# SCH_TabletComputer-SurfacePi_2024-07-24.net
KiCad netlist of a schematic drawn in EasyEDA
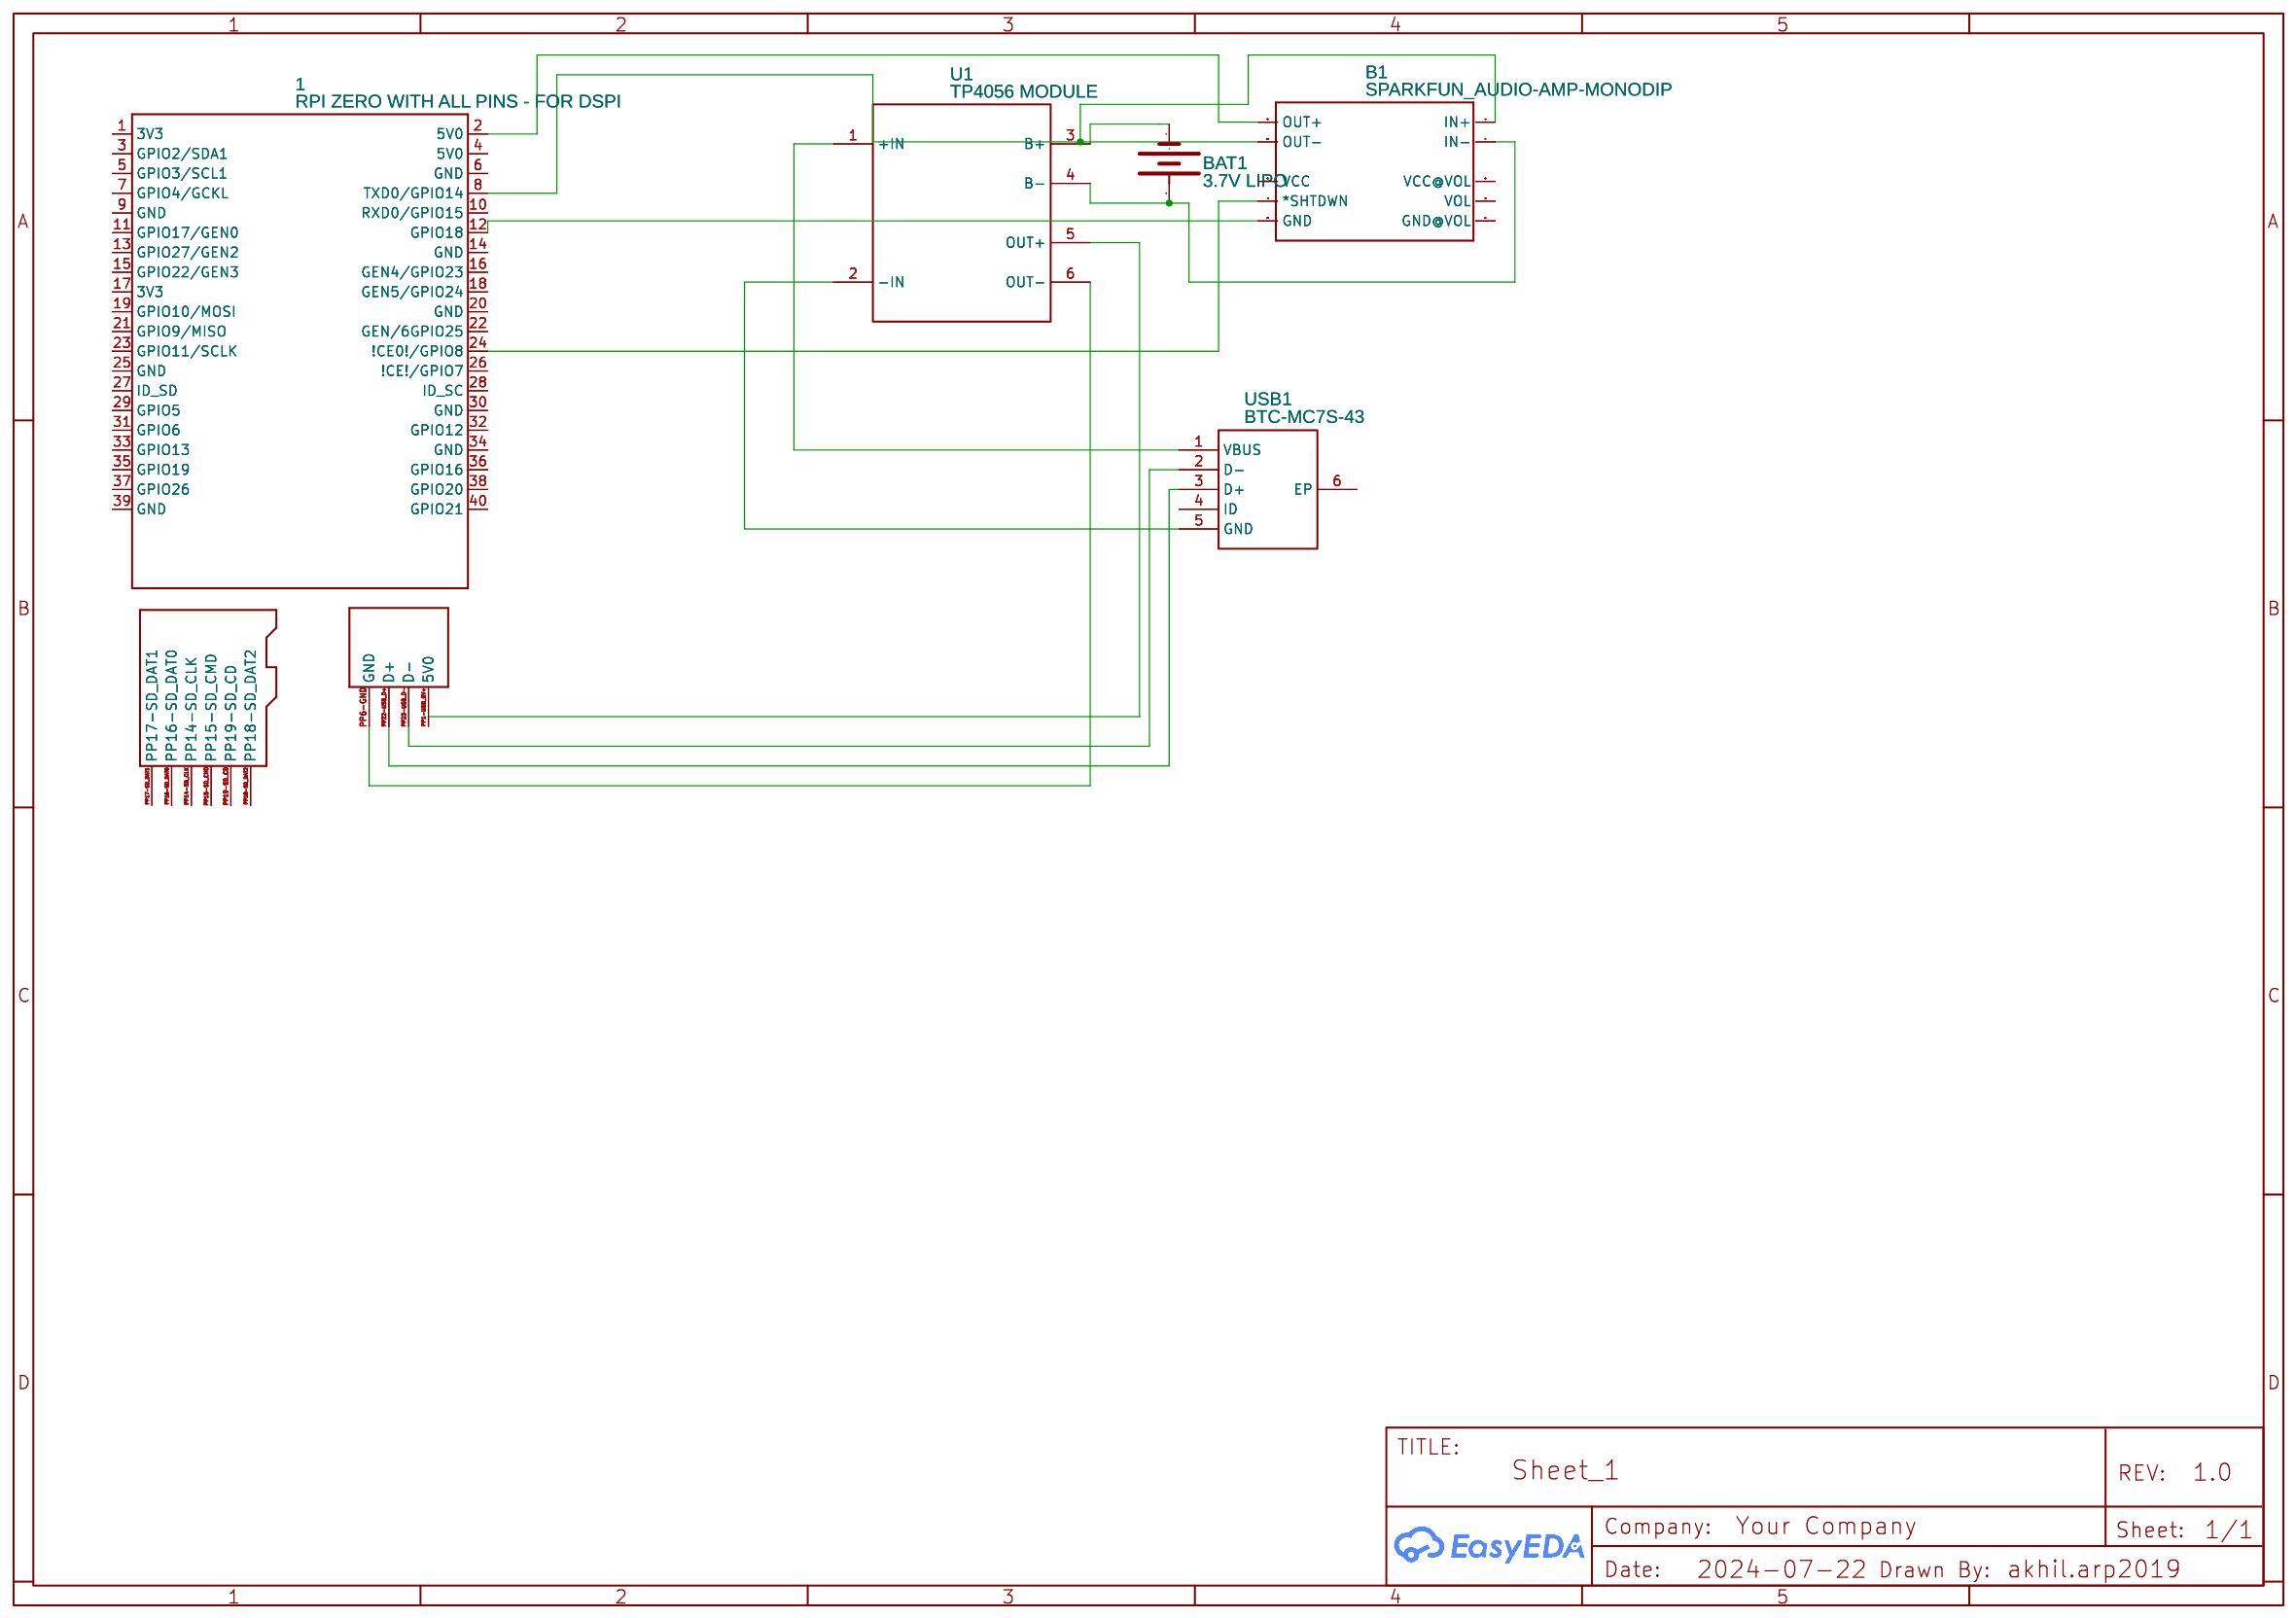
[diagram p0: schematic sheet]

(export (version "E")
  (design (tool "Eeschema 10.0.6"))
  (components
    (comp (ref "1")
      (value "RPI ZERO WITH ALL PINS - FOR DSPI")
      (libsource (lib "") (part "RPI ZERO WITH ALL PINS - FOR DSPI"))
    )
    (comp (ref "B1")
      (value "SPARKFUN_AUDIO-AMP-MONODIP")
      (libsource (lib "") (part "SPARKFUN_AUDIO-AMP-MONODIP"))
    )
    (comp (ref "BAT1") (value "3.7V LIPO") (libsource (lib "") (part "3.7V LIPO")))
    (comp (ref "U1") (value "TP4056 MODULE") (libsource (lib "") (part "TP4056 MODULE")))
    (comp (ref "USB1")
      (value "BTC-MC7S-43")
      (fields (field (name "Manufacturer") "DGBZ(东莞博众)"))
      (libsource (lib "") (part "BTC-MC7S-43"))
    )
  )
  (nets
    (net (code "1") (name "Net-(1-!CE0!{slash}GPIO8)") (class "Default")
      (node (ref "1") (pin "24") (pinfunction "!CE0!/GPIO8_24") (pintype "bidirectional"))
      (node (ref "B1") (pin "S") (pinfunction "*SHTDWN_S") (pintype "bidirectional"))
    )
    (net (code "2") (name "Net-(1-5V0-Pad2)") (class "Default")
      (node (ref "1") (pin "2") (pinfunction "5V0_2") (pintype "bidirectional"))
      (node (ref "B1") (pin "OUT+") (pinfunction "OUT+_OUT+") (pintype "bidirectional"))
    )
    (net (code "3") (name "Net-(1-D+)") (class "Default")
      (node (ref "1") (pin "PP22-USB_D+") (pinfunction "D+_PP22-USB_D+") (pintype "bidirectional"))
      (node (ref "USB1") (pin "3") (pinfunction "D+_3") (pintype "unspecified"))
    )
    (net (code "4") (name "Net-(1-D-)") (class "Default")
      (node (ref "1") (pin "PP23-USB_D-") (pinfunction "D-_PP23-USB_D-") (pintype "bidirectional"))
      (node (ref "USB1") (pin "2") (pinfunction "D-_2") (pintype "unspecified"))
    )
    (net (code "5") (name "Net-(1-GPIO18)") (class "Default")
      (node (ref "1") (pin "12") (pinfunction "GPIO18_12") (pintype "bidirectional"))
      (node (ref "B1") (pin "PWR-") (pinfunction "GND_PWR-") (pintype "bidirectional"))
    )
    (net (code "6") (name "Net-(1-TXD0{slash}GPIO14)") (class "Default")
      (node (ref "1") (pin "8") (pinfunction "TXD0/GPIO14_8") (pintype "bidirectional"))
      (node (ref "B1") (pin "IN+") (pinfunction "IN+_IN+") (pintype "bidirectional"))
      (node (ref "B1") (pin "OUT-") (pinfunction "OUT-_OUT-") (pintype "bidirectional"))
    )
    (net (code "7") (name "Net-(U1-+IN)") (class "Default")
      (node (ref "U1") (pin "1") (pinfunction "+IN_1") (pintype "unspecified"))
      (node (ref "USB1") (pin "1") (pinfunction "VBUS_1") (pintype "unspecified"))
    )
    (net (code "8") (name "Net-(U1--IN)") (class "Default")
      (node (ref "U1") (pin "2") (pinfunction "-IN_2") (pintype "unspecified"))
      (node (ref "USB1") (pin "5") (pinfunction "GND_5") (pintype "unspecified"))
    )
    (net (code "9") (name "Net-(U1-B+)") (class "Default")
      (node (ref "BAT1") (pin "-") (pinfunction "-_-") (pintype "passive"))
      (node (ref "U1") (pin "3") (pinfunction "B+_3") (pintype "unspecified"))
    )
    (net (code "10") (name "Net-(U1-B-)") (class "Default")
      (node (ref "B1") (pin "IN-") (pinfunction "IN-_IN-") (pintype "bidirectional"))
      (node (ref "BAT1") (pin "+") (pinfunction "+_+") (pintype "passive"))
      (node (ref "U1") (pin "4") (pinfunction "B-_4") (pintype "unspecified"))
    )
    (net (code "11") (name "Net-(U1-OUT+)") (class "Default")
      (node (ref "1") (pin "PP1-USB_5V+") (pinfunction "5V0_PP1-USB_5V+") (pintype "bidirectional"))
      (node (ref "U1") (pin "5") (pinfunction "OUT+_5") (pintype "unspecified"))
    )
    (net (code "12") (name "Net-(U1-OUT-)") (class "Default")
      (node (ref "1") (pin "PP6-GND") (pinfunction "GND_PP6-GND") (pintype "bidirectional"))
      (node (ref "U1") (pin "6") (pinfunction "OUT-_6") (pintype "unspecified"))
    )
    (net (code "13") (name "unconnected-(1-!CE!{slash}GPIO7-Pad26)") (class "Default")
      (node (ref "1") (pin "26") (pinfunction "!CE!/GPIO7_26") (pintype "bidirectional"))
    )
    (net (code "14") (name "unconnected-(1-3V3-Pad1)") (class "Default")
      (node (ref "1") (pin "1") (pinfunction "3V3_1") (pintype "bidirectional"))
    )
    (net (code "15") (name "unconnected-(1-3V3-Pad17)") (class "Default")
      (node (ref "1") (pin "17") (pinfunction "3V3_17") (pintype "bidirectional"))
    )
    (net (code "16") (name "unconnected-(1-5V0-Pad4)") (class "Default")
      (node (ref "1") (pin "4") (pinfunction "5V0_4") (pintype "bidirectional"))
    )
    (net (code "17") (name "unconnected-(1-GEN4{slash}GPIO23-Pad16)") (class "Default")
      (node (ref "1") (pin "16") (pinfunction "GEN4/GPIO23_16") (pintype "bidirectional"))
    )
    (net (code "18") (name "unconnected-(1-GEN5{slash}GPIO24-Pad18)") (class "Default")
      (node (ref "1") (pin "18") (pinfunction "GEN5/GPIO24_18") (pintype "bidirectional"))
    )
    (net (code "19") (name "unconnected-(1-GEN{slash}6GPIO25-Pad22)") (class "Default")
      (node (ref "1") (pin "22") (pinfunction "GEN/6GPIO25_22") (pintype "bidirectional"))
    )
    (net (code "20") (name "unconnected-(1-GND-Pad6)") (class "Default")
      (node (ref "1") (pin "6") (pinfunction "GND_6") (pintype "bidirectional"))
    )
    (net (code "21") (name "unconnected-(1-GND-Pad9)") (class "Default")
      (node (ref "1") (pin "9") (pinfunction "GND_9") (pintype "bidirectional"))
    )
    (net (code "22") (name "unconnected-(1-GND-Pad14)") (class "Default")
      (node (ref "1") (pin "14") (pinfunction "GND_14") (pintype "bidirectional"))
    )
    (net (code "23") (name "unconnected-(1-GND-Pad20)") (class "Default")
      (node (ref "1") (pin "20") (pinfunction "GND_20") (pintype "bidirectional"))
    )
    (net (code "24") (name "unconnected-(1-GND-Pad25)") (class "Default")
      (node (ref "1") (pin "25") (pinfunction "GND_25") (pintype "bidirectional"))
    )
    (net (code "25") (name "unconnected-(1-GND-Pad30)") (class "Default")
      (node (ref "1") (pin "30") (pinfunction "GND_30") (pintype "bidirectional"))
    )
    (net (code "26") (name "unconnected-(1-GND-Pad34)") (class "Default")
      (node (ref "1") (pin "34") (pinfunction "GND_34") (pintype "bidirectional"))
    )
    (net (code "27") (name "unconnected-(1-GND-Pad39)") (class "Default")
      (node (ref "1") (pin "39") (pinfunction "GND_39") (pintype "bidirectional"))
    )
    (net (code "28") (name "unconnected-(1-GPIO2{slash}SDA1-Pad3)") (class "Default")
      (node (ref "1") (pin "3") (pinfunction "GPIO2/SDA1_3") (pintype "bidirectional"))
    )
    (net (code "29") (name "unconnected-(1-GPIO3{slash}SCL1-Pad5)") (class "Default")
      (node (ref "1") (pin "5") (pinfunction "GPIO3/SCL1_5") (pintype "bidirectional"))
    )
    (net (code "30") (name "unconnected-(1-GPIO4{slash}GCKL-Pad7)") (class "Default")
      (node (ref "1") (pin "7") (pinfunction "GPIO4/GCKL_7") (pintype "bidirectional"))
    )
    (net (code "31") (name "unconnected-(1-GPIO5-Pad29)") (class "Default")
      (node (ref "1") (pin "29") (pinfunction "GPIO5_29") (pintype "bidirectional"))
    )
    (net (code "32") (name "unconnected-(1-GPIO6-Pad31)") (class "Default")
      (node (ref "1") (pin "31") (pinfunction "GPIO6_31") (pintype "bidirectional"))
    )
    (net (code "33") (name "unconnected-(1-GPIO9{slash}MISO-Pad21)") (class "Default")
      (node (ref "1") (pin "21") (pinfunction "GPIO9/MISO_21") (pintype "bidirectional"))
    )
    (net (code "34") (name "unconnected-(1-GPIO10{slash}MOSI-Pad19)") (class "Default")
      (node (ref "1") (pin "19") (pinfunction "GPIO10/MOSI_19") (pintype "bidirectional"))
    )
    (net (code "35") (name "unconnected-(1-GPIO11{slash}SCLK-Pad23)") (class "Default")
      (node (ref "1") (pin "23") (pinfunction "GPIO11/SCLK_23") (pintype "bidirectional"))
    )
    (net (code "36") (name "unconnected-(1-GPIO12-Pad32)") (class "Default")
      (node (ref "1") (pin "32") (pinfunction "GPIO12_32") (pintype "bidirectional"))
    )
    (net (code "37") (name "unconnected-(1-GPIO13-Pad33)") (class "Default")
      (node (ref "1") (pin "33") (pinfunction "GPIO13_33") (pintype "bidirectional"))
    )
    (net (code "38") (name "unconnected-(1-GPIO16-Pad36)") (class "Default")
      (node (ref "1") (pin "36") (pinfunction "GPIO16_36") (pintype "bidirectional"))
    )
    (net (code "39") (name "unconnected-(1-GPIO17{slash}GEN0-Pad11)") (class "Default")
      (node (ref "1") (pin "11") (pinfunction "GPIO17/GEN0_11") (pintype "bidirectional"))
    )
    (net (code "40") (name "unconnected-(1-GPIO19-Pad35)") (class "Default")
      (node (ref "1") (pin "35") (pinfunction "GPIO19_35") (pintype "bidirectional"))
    )
    (net (code "41") (name "unconnected-(1-GPIO20-Pad38)") (class "Default")
      (node (ref "1") (pin "38") (pinfunction "GPIO20_38") (pintype "bidirectional"))
    )
    (net (code "42") (name "unconnected-(1-GPIO21-Pad40)") (class "Default")
      (node (ref "1") (pin "40") (pinfunction "GPIO21_40") (pintype "bidirectional"))
    )
    (net (code "43") (name "unconnected-(1-GPIO22{slash}GEN3-Pad15)") (class "Default")
      (node (ref "1") (pin "15") (pinfunction "GPIO22/GEN3_15") (pintype "bidirectional"))
    )
    (net (code "44") (name "unconnected-(1-GPIO26-Pad37)") (class "Default")
      (node (ref "1") (pin "37") (pinfunction "GPIO26_37") (pintype "bidirectional"))
    )
    (net (code "45") (name "unconnected-(1-GPIO27{slash}GEN2-Pad13)") (class "Default")
      (node (ref "1") (pin "13") (pinfunction "GPIO27/GEN2_13") (pintype "bidirectional"))
    )
    (net (code "46") (name "unconnected-(1-ID_SC-Pad28)") (class "Default")
      (node (ref "1") (pin "28") (pinfunction "ID_SC_28") (pintype "bidirectional"))
    )
    (net (code "47") (name "unconnected-(1-ID_SD-Pad27)") (class "Default")
      (node (ref "1") (pin "27") (pinfunction "ID_SD_27") (pintype "bidirectional"))
    )
    (net (code "48") (name "unconnected-(1-PadPP14-SD_CLK)") (class "Default")
      (node (ref "1") (pin "PP14-SD_CLK") (pinfunction "PP14-SD_CLK_PP14-SD_CLK") (pintype "bidirectional"))
    )
    (net (code "49") (name "unconnected-(1-PadPP15-SD_CMD)") (class "Default")
      (node (ref "1") (pin "PP15-SD_CMD") (pinfunction "PP15-SD_CMD_PP15-SD_CMD") (pintype "bidirectional"))
    )
    (net (code "50") (name "unconnected-(1-PadPP16-SD_DAT0)") (class "Default")
      (node (ref "1") (pin "PP16-SD_DAT0") (pinfunction "PP16-SD_DAT0_PP16-SD_DAT0") (pintype "bidirectional"))
    )
    (net (code "51") (name "unconnected-(1-PadPP17-SD_DAT1)") (class "Default")
      (node (ref "1") (pin "PP17-SD_DAT1") (pinfunction "PP17-SD_DAT1_PP17-SD_DAT1") (pintype "bidirectional"))
    )
    (net (code "52") (name "unconnected-(1-PadPP18-SD_DAT2)") (class "Default")
      (node (ref "1") (pin "PP18-SD_DAT2") (pinfunction "PP18-SD_DAT2_PP18-SD_DAT2") (pintype "bidirectional"))
    )
    (net (code "53") (name "unconnected-(1-PadPP19-SD_CD)") (class "Default")
      (node (ref "1") (pin "PP19-SD_CD") (pinfunction "PP19-SD_CD_PP19-SD_CD") (pintype "bidirectional"))
    )
    (net (code "54") (name "unconnected-(1-RXD0{slash}GPIO15-Pad10)") (class "Default")
      (node (ref "1") (pin "10") (pinfunction "RXD0/GPIO15_10") (pintype "bidirectional"))
    )
    (net (code "55") (name "unconnected-(B1-GND@VOL-PadVOL-)") (class "Default")
      (node (ref "B1") (pin "VOL-") (pinfunction "GND@VOL_VOL-") (pintype "bidirectional"))
    )
    (net (code "56") (name "unconnected-(B1-PadVOL)") (class "Default")
      (node (ref "B1") (pin "VOL") (pinfunction "VOL_VOL") (pintype "bidirectional"))
    )
    (net (code "57") (name "unconnected-(B1-VCC-PadPWR+)") (class "Default")
      (node (ref "B1") (pin "PWR+") (pinfunction "VCC_PWR+") (pintype "bidirectional"))
    )
    (net (code "58") (name "unconnected-(B1-VCC@VOL-PadVOL+)") (class "Default")
      (node (ref "B1") (pin "VOL+") (pinfunction "VCC@VOL_VOL+") (pintype "bidirectional"))
    )
    (net (code "59") (name "unconnected-(USB1-EP-Pad6)") (class "Default")
      (node (ref "USB1") (pin "6") (pinfunction "EP_6") (pintype "unspecified"))
    )
    (net (code "60") (name "unconnected-(USB1-ID-Pad4)") (class "Default")
      (node (ref "USB1") (pin "4") (pinfunction "ID_4") (pintype "unspecified"))
    )
  )
)
